# sa-22c-microsemi-connector.net
KiCad netlist of a schematic drawn in EAGLE
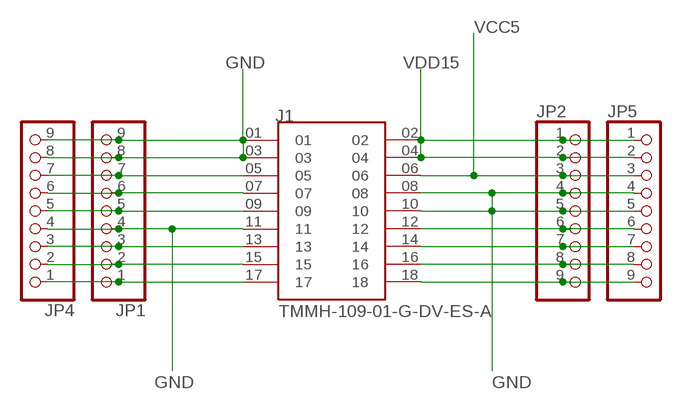
[diagram p0: schematic, sheet 1]

(export (version "E")
  (design (tool "Eeschema 10.0.6"))
  (components
    (comp (ref "J1")
      (value "TMMH-109-01-G-DV-ES-A")
      (footprint "eagle-import:SAMTEC_TMMH-109-01-G-DV-ES-A")
      (fields (field (name "MANUFACTURER") "Samtec"))
      (libsource (lib "eagle-import") (part "TMMH-109-01-G-DV-ES-A"))
    )
    (comp (ref "JP1")
      (value "PINHD-1X9")
      (footprint "eagle-import:1X09")
      (libsource (lib "eagle-import") (part "PINHD-1X9"))
    )
    (comp (ref "JP2")
      (value "PINHD-1X9")
      (footprint "eagle-import:1X09")
      (libsource (lib "eagle-import") (part "PINHD-1X9"))
    )
    (comp (ref "JP4")
      (value "PINHD-1X9")
      (footprint "eagle-import:1X09")
      (libsource (lib "eagle-import") (part "PINHD-1X9"))
    )
    (comp (ref "JP5")
      (value "PINHD-1X9")
      (footprint "eagle-import:1X09")
      (libsource (lib "eagle-import") (part "PINHD-1X9"))
    )
  )
  (nets
    (net (code "1") (name "/GND") (class "Default")
      (node (ref "J1") (pin "01") (pinfunction "01_01") (pintype "passive"))
      (node (ref "J1") (pin "03") (pinfunction "03_03") (pintype "passive"))
      (node (ref "J1") (pin "08") (pinfunction "08_08") (pintype "passive"))
      (node (ref "J1") (pin "10") (pinfunction "10_10") (pintype "passive"))
      (node (ref "J1") (pin "11") (pinfunction "11_11") (pintype "passive"))
      (node (ref "JP1") (pin "4") (pinfunction "4_4") (pintype "passive"))
      (node (ref "JP1") (pin "8") (pinfunction "8_8") (pintype "passive"))
      (node (ref "JP1") (pin "9") (pinfunction "9_9") (pintype "passive"))
      (node (ref "JP2") (pin "4") (pinfunction "4_4") (pintype "passive"))
      (node (ref "JP2") (pin "5") (pinfunction "5_5") (pintype "passive"))
      (node (ref "JP4") (pin "4") (pinfunction "4_4") (pintype "passive"))
      (node (ref "JP4") (pin "8") (pinfunction "8_8") (pintype "passive"))
      (node (ref "JP4") (pin "9") (pinfunction "9_9") (pintype "passive"))
      (node (ref "JP5") (pin "4") (pinfunction "4_4") (pintype "passive"))
      (node (ref "JP5") (pin "5") (pinfunction "5_5") (pintype "passive"))
    )
    (net (code "2") (name "/VCC5") (class "Default")
      (node (ref "J1") (pin "06") (pinfunction "06_06") (pintype "passive"))
      (node (ref "JP2") (pin "3") (pinfunction "3_3") (pintype "passive"))
      (node (ref "JP5") (pin "3") (pinfunction "3_3") (pintype "passive"))
    )
    (net (code "3") (name "/VDD15") (class "Default")
      (node (ref "J1") (pin "02") (pinfunction "02_02") (pintype "passive"))
      (node (ref "J1") (pin "04") (pinfunction "04_04") (pintype "passive"))
      (node (ref "JP2") (pin "1") (pinfunction "1_1") (pintype "passive"))
      (node (ref "JP2") (pin "2") (pinfunction "2_2") (pintype "passive"))
      (node (ref "JP5") (pin "1") (pinfunction "1_1") (pintype "passive"))
      (node (ref "JP5") (pin "2") (pinfunction "2_2") (pintype "passive"))
    )
    (net (code "4") (name "Net-(J1-Pad05)") (class "Default")
      (node (ref "J1") (pin "05") (pinfunction "05_05") (pintype "passive"))
      (node (ref "JP1") (pin "7") (pinfunction "7_7") (pintype "passive"))
      (node (ref "JP4") (pin "7") (pinfunction "7_7") (pintype "passive"))
    )
    (net (code "5") (name "Net-(J1-Pad07)") (class "Default")
      (node (ref "J1") (pin "07") (pinfunction "07_07") (pintype "passive"))
      (node (ref "JP1") (pin "6") (pinfunction "6_6") (pintype "passive"))
      (node (ref "JP4") (pin "6") (pinfunction "6_6") (pintype "passive"))
    )
    (net (code "6") (name "Net-(J1-Pad09)") (class "Default")
      (node (ref "J1") (pin "09") (pinfunction "09_09") (pintype "passive"))
      (node (ref "JP1") (pin "5") (pinfunction "5_5") (pintype "passive"))
      (node (ref "JP4") (pin "5") (pinfunction "5_5") (pintype "passive"))
    )
    (net (code "7") (name "Net-(J1-Pad12)") (class "Default")
      (node (ref "J1") (pin "12") (pinfunction "12_12") (pintype "passive"))
      (node (ref "JP2") (pin "6") (pinfunction "6_6") (pintype "passive"))
      (node (ref "JP5") (pin "6") (pinfunction "6_6") (pintype "passive"))
    )
    (net (code "8") (name "Net-(J1-Pad13)") (class "Default")
      (node (ref "J1") (pin "13") (pinfunction "13_13") (pintype "passive"))
      (node (ref "JP1") (pin "3") (pinfunction "3_3") (pintype "passive"))
      (node (ref "JP4") (pin "3") (pinfunction "3_3") (pintype "passive"))
    )
    (net (code "9") (name "Net-(J1-Pad14)") (class "Default")
      (node (ref "J1") (pin "14") (pinfunction "14_14") (pintype "passive"))
      (node (ref "JP2") (pin "7") (pinfunction "7_7") (pintype "passive"))
      (node (ref "JP5") (pin "7") (pinfunction "7_7") (pintype "passive"))
    )
    (net (code "10") (name "Net-(J1-Pad15)") (class "Default")
      (node (ref "J1") (pin "15") (pinfunction "15_15") (pintype "passive"))
      (node (ref "JP1") (pin "2") (pinfunction "2_2") (pintype "passive"))
      (node (ref "JP4") (pin "2") (pinfunction "2_2") (pintype "passive"))
    )
    (net (code "11") (name "Net-(J1-Pad16)") (class "Default")
      (node (ref "J1") (pin "16") (pinfunction "16_16") (pintype "passive"))
      (node (ref "JP2") (pin "8") (pinfunction "8_8") (pintype "passive"))
      (node (ref "JP5") (pin "8") (pinfunction "8_8") (pintype "passive"))
    )
    (net (code "12") (name "Net-(J1-Pad17)") (class "Default")
      (node (ref "J1") (pin "17") (pinfunction "17_17") (pintype "passive"))
      (node (ref "JP1") (pin "1") (pinfunction "1_1") (pintype "passive"))
      (node (ref "JP4") (pin "1") (pinfunction "1_1") (pintype "passive"))
    )
    (net (code "13") (name "Net-(J1-Pad18)") (class "Default")
      (node (ref "J1") (pin "18") (pinfunction "18_18") (pintype "passive"))
      (node (ref "JP2") (pin "9") (pinfunction "9_9") (pintype "passive"))
      (node (ref "JP5") (pin "9") (pinfunction "9_9") (pintype "passive"))
    )
  )
)
